# Arduino_XBee_sensing_relays.net
KiCad netlist of a schematic drawn in EAGLE
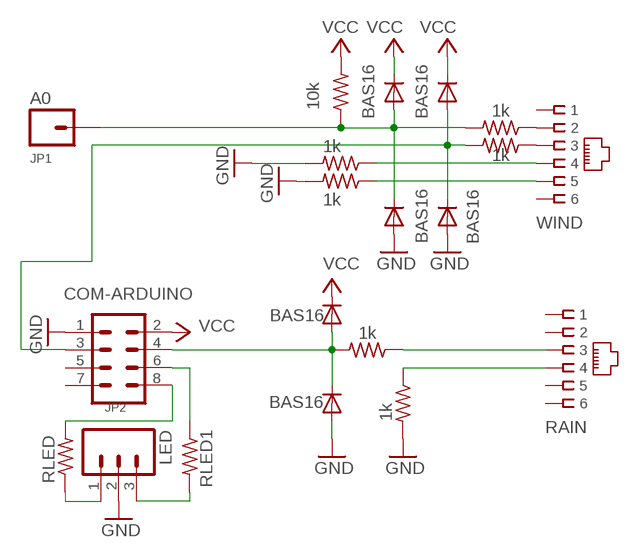
[diagram p0: schematic, sheet 1]

(export (version "E")
  (design (tool "Eeschema 10.0.6"))
  (components
    (comp (ref "A0")
      (value "JP1")
      (footprint "eagle-import:1X01")
      (libsource (lib "eagle-import") (part "M01PTH"))
    )
    (comp (ref "COM-ARDUINO")
      (value "JP2")
      (footprint "eagle-import:2X4")
      (libsource (lib "eagle-import") (part "M04X2"))
    )
    (comp (ref "D1")
      (value "BAS16")
      (footprint "eagle-import:SOD-323")
      (fields (field (name "PROD_ID") "DIO-09646"))
      (libsource (lib "eagle-import") (part "DIODESOD"))
    )
    (comp (ref "D2")
      (value "BAS16")
      (footprint "eagle-import:SOD-323")
      (fields (field (name "PROD_ID") "DIO-09646"))
      (libsource (lib "eagle-import") (part "DIODESOD"))
    )
    (comp (ref "D3")
      (value "BAS16")
      (footprint "eagle-import:SOD-323")
      (fields (field (name "PROD_ID") "DIO-09646"))
      (libsource (lib "eagle-import") (part "DIODESOD"))
    )
    (comp (ref "D4")
      (value "BAS16")
      (footprint "eagle-import:SOD-323")
      (fields (field (name "PROD_ID") "DIO-09646"))
      (libsource (lib "eagle-import") (part "DIODESOD"))
    )
    (comp (ref "D5")
      (value "BAS16")
      (footprint "eagle-import:SOD-323")
      (fields (field (name "PROD_ID") "DIO-09646"))
      (libsource (lib "eagle-import") (part "DIODESOD"))
    )
    (comp (ref "D6")
      (value "BAS16")
      (footprint "eagle-import:SOD-323")
      (fields (field (name "PROD_ID") "DIO-09646"))
      (libsource (lib "eagle-import") (part "DIODESOD"))
    )
    (comp (ref "LED")
      (value "M03PTH")
      (footprint "eagle-import:1X03")
      (libsource (lib "eagle-import") (part "M03PTH"))
    )
    (comp (ref "R1")
      (value "1k")
      (footprint "eagle-import:M0805")
      (libsource (lib "eagle-import") (part "R-US_M0805"))
    )
    (comp (ref "R2")
      (value "10k")
      (footprint "eagle-import:M0805")
      (libsource (lib "eagle-import") (part "R-US_M0805"))
    )
    (comp (ref "R3")
      (value "1k")
      (footprint "eagle-import:M0805")
      (libsource (lib "eagle-import") (part "R-US_M0805"))
    )
    (comp (ref "R4")
      (value "1k")
      (footprint "eagle-import:M0805")
      (libsource (lib "eagle-import") (part "R-US_M0805"))
    )
    (comp (ref "R5")
      (value "1k")
      (footprint "eagle-import:M0805")
      (libsource (lib "eagle-import") (part "R-US_M0805"))
    )
    (comp (ref "R7")
      (value "1k")
      (footprint "eagle-import:M0805")
      (libsource (lib "eagle-import") (part "R-US_M0805"))
    )
    (comp (ref "R8")
      (value "1k")
      (footprint "eagle-import:M0805")
      (libsource (lib "eagle-import") (part "R-US_M0805"))
    )
    (comp (ref "RAIN")
      (value "RAIN")
      (footprint "eagle-import:RJ11-NO_SHIELD")
      (libsource (lib "eagle-import") (part "RJ11-2X"))
    )
    (comp (ref "RLED")
      (value "R-US_M0805")
      (footprint "eagle-import:M0805")
      (libsource (lib "eagle-import") (part "R-US_M0805"))
    )
    (comp (ref "RLED1")
      (value "R-US_M0805")
      (footprint "eagle-import:M0805")
      (libsource (lib "eagle-import") (part "R-US_M0805"))
    )
    (comp (ref "WIND")
      (value "WIND")
      (footprint "eagle-import:RJ11-NO_SHIELD")
      (libsource (lib "eagle-import") (part "RJ11-2X"))
    )
  )
  (nets
    (net (code "1") (name "GND") (class "Default")
      (node (ref "COM-ARDUINO") (pin "1") (pinfunction "1_1") (pintype "passive"))
      (node (ref "D2") (pin "2") (pinfunction "A_2") (pintype "passive"))
      (node (ref "D4") (pin "2") (pinfunction "A_2") (pintype "passive"))
      (node (ref "D6") (pin "2") (pinfunction "A_2") (pintype "passive"))
      (node (ref "LED") (pin "2") (pinfunction "2_2") (pintype "passive"))
      (node (ref "R4") (pin "2") (pinfunction "2_2") (pintype "passive"))
      (node (ref "R5") (pin "2") (pinfunction "2_2") (pintype "passive"))
      (node (ref "R8") (pin "2") (pinfunction "2_2") (pintype "passive"))
    )
    (net (code "2") (name "Net-(COM-ARDUINO-Pad6)") (class "Default")
      (node (ref "COM-ARDUINO") (pin "6") (pinfunction "6_6") (pintype "passive"))
      (node (ref "RLED1") (pin "1") (pinfunction "1_1") (pintype "passive"))
    )
    (net (code "3") (name "Net-(COM-ARDUINO-Pad8)") (class "Default")
      (node (ref "COM-ARDUINO") (pin "8") (pinfunction "8_8") (pintype "passive"))
      (node (ref "RLED") (pin "2") (pinfunction "2_2") (pintype "passive"))
    )
    (net (code "4") (name "Net-(D1-A)") (class "Default")
      (node (ref "A0") (pin "1") (pinfunction "1_1") (pintype "passive"))
      (node (ref "D1") (pin "2") (pinfunction "A_2") (pintype "passive"))
      (node (ref "D2") (pin "1") (pinfunction "C_1") (pintype "passive"))
      (node (ref "R1") (pin "2") (pinfunction "2_2") (pintype "passive"))
      (node (ref "R2") (pin "1") (pinfunction "1_1") (pintype "passive"))
    )
    (net (code "5") (name "Net-(D3-A)") (class "Default")
      (node (ref "COM-ARDUINO") (pin "3") (pinfunction "3_3") (pintype "passive"))
      (node (ref "D3") (pin "2") (pinfunction "A_2") (pintype "passive"))
      (node (ref "D4") (pin "1") (pinfunction "C_1") (pintype "passive"))
      (node (ref "R3") (pin "2") (pinfunction "2_2") (pintype "passive"))
    )
    (net (code "6") (name "Net-(D5-A)") (class "Default")
      (node (ref "COM-ARDUINO") (pin "4") (pinfunction "4_4") (pintype "passive"))
      (node (ref "D5") (pin "2") (pinfunction "A_2") (pintype "passive"))
      (node (ref "D6") (pin "1") (pinfunction "C_1") (pintype "passive"))
      (node (ref "R7") (pin "2") (pinfunction "2_2") (pintype "passive"))
    )
    (net (code "7") (name "Net-(LED-Pad1)") (class "Default")
      (node (ref "LED") (pin "1") (pinfunction "1_1") (pintype "passive"))
      (node (ref "RLED") (pin "1") (pinfunction "1_1") (pintype "passive"))
    )
    (net (code "8") (name "Net-(LED-Pad3)") (class "Default")
      (node (ref "LED") (pin "3") (pinfunction "3_3") (pintype "passive"))
      (node (ref "RLED1") (pin "2") (pinfunction "2_2") (pintype "passive"))
    )
    (net (code "9") (name "Net-(R1-Pad1)") (class "Default")
      (node (ref "R1") (pin "1") (pinfunction "1_1") (pintype "passive"))
      (node (ref "WIND") (pin "2") (pinfunction "2_2") (pintype "passive"))
    )
    (net (code "10") (name "Net-(R3-Pad1)") (class "Default")
      (node (ref "R3") (pin "1") (pinfunction "1_1") (pintype "passive"))
      (node (ref "WIND") (pin "3") (pinfunction "3_3") (pintype "passive"))
    )
    (net (code "11") (name "Net-(R4-Pad1)") (class "Default")
      (node (ref "R4") (pin "1") (pinfunction "1_1") (pintype "passive"))
      (node (ref "WIND") (pin "4") (pinfunction "4_4") (pintype "passive"))
    )
    (net (code "12") (name "Net-(R5-Pad1)") (class "Default")
      (node (ref "R5") (pin "1") (pinfunction "1_1") (pintype "passive"))
      (node (ref "WIND") (pin "5") (pinfunction "5_5") (pintype "passive"))
    )
    (net (code "13") (name "Net-(R7-Pad1)") (class "Default")
      (node (ref "R7") (pin "1") (pinfunction "1_1") (pintype "passive"))
      (node (ref "RAIN") (pin "3") (pinfunction "3_3") (pintype "passive"))
    )
    (net (code "14") (name "Net-(R8-Pad1)") (class "Default")
      (node (ref "R8") (pin "1") (pinfunction "1_1") (pintype "passive"))
      (node (ref "RAIN") (pin "4") (pinfunction "4_4") (pintype "passive"))
    )
    (net (code "15") (name "VCC") (class "Default")
      (node (ref "COM-ARDUINO") (pin "2") (pinfunction "2_2") (pintype "passive"))
      (node (ref "D1") (pin "1") (pinfunction "C_1") (pintype "passive"))
      (node (ref "D3") (pin "1") (pinfunction "C_1") (pintype "passive"))
      (node (ref "D5") (pin "1") (pinfunction "C_1") (pintype "passive"))
      (node (ref "R2") (pin "2") (pinfunction "2_2") (pintype "passive"))
    )
    (net (code "16") (name "unconnected-(COM-ARDUINO-Pad5)") (class "Default")
      (node (ref "COM-ARDUINO") (pin "5") (pinfunction "5_5") (pintype "passive"))
    )
    (net (code "17") (name "unconnected-(COM-ARDUINO-Pad7)") (class "Default")
      (node (ref "COM-ARDUINO") (pin "7") (pinfunction "7_7") (pintype "passive"))
    )
    (net (code "18") (name "unconnected-(RAIN-Pad1)") (class "Default")
      (node (ref "RAIN") (pin "1") (pinfunction "1_1") (pintype "passive"))
    )
    (net (code "19") (name "unconnected-(RAIN-Pad2)") (class "Default")
      (node (ref "RAIN") (pin "2") (pinfunction "2_2") (pintype "passive"))
    )
    (net (code "20") (name "unconnected-(RAIN-Pad5)") (class "Default")
      (node (ref "RAIN") (pin "5") (pinfunction "5_5") (pintype "passive"))
    )
    (net (code "21") (name "unconnected-(RAIN-Pad6)") (class "Default")
      (node (ref "RAIN") (pin "6") (pinfunction "6_6") (pintype "passive"))
    )
    (net (code "22") (name "unconnected-(WIND-Pad1)") (class "Default")
      (node (ref "WIND") (pin "1") (pinfunction "1_1") (pintype "passive"))
    )
    (net (code "23") (name "unconnected-(WIND-Pad6)") (class "Default")
      (node (ref "WIND") (pin "6") (pinfunction "6_6") (pintype "passive"))
    )
  )
)
